# line_follower_INCOMPLETE.net
KiCad netlist of a schematic drawn in EAGLE
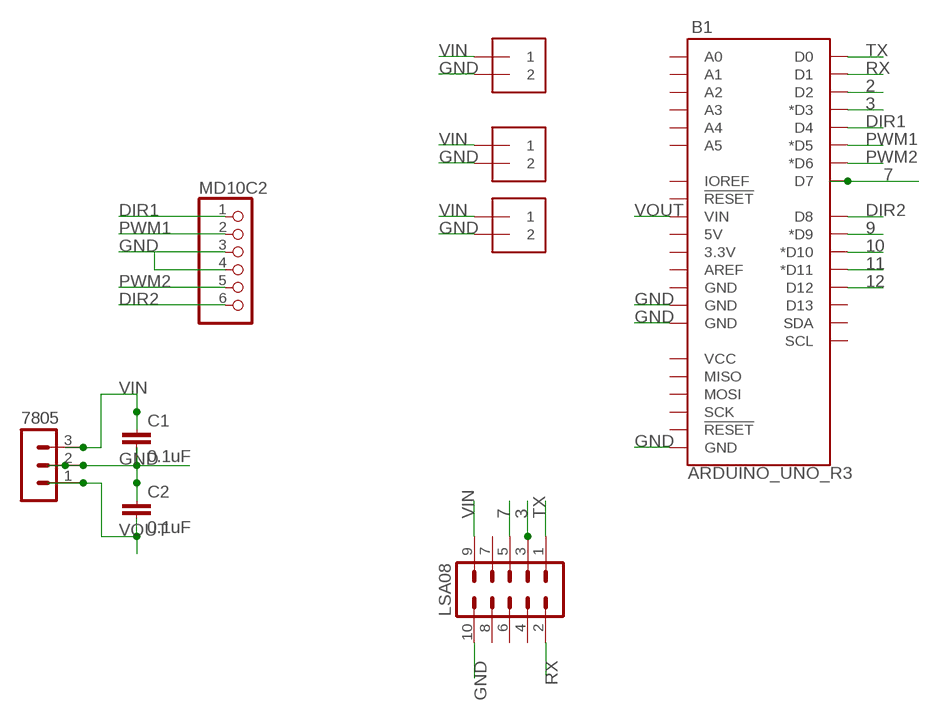
[diagram p0: schematic, sheet 1]

(export (version "E")
  (design (tool "Eeschema 10.0.6"))
  (components
    (comp (ref "7805")
      (value "MA03-1")
      (footprint "eagle-import:MA03-1")
      (libsource (lib "eagle-import") (part "MA03-1"))
    )
    (comp (ref "B1")
      (value "ARDUINO_UNO_R3")
      (footprint "eagle-import:ARDUINO_R3")
      (libsource (lib "eagle-import") (part "ARDUINO_UNO_R3"))
    )
    (comp (ref "C1")
      (value "0.1uF")
      (footprint "eagle-import:CAP-PTH-SMALL-KIT")
      (libsource (lib "eagle-import") (part "0.1UF-KIT-EZ-50V-20%"))
    )
    (comp (ref "C2")
      (value "0.1uF")
      (footprint "eagle-import:CAP-PTH-SMALL-KIT")
      (libsource (lib "eagle-import") (part "0.1UF-KIT-EZ-50V-20%"))
    )
    (comp (ref "LSA08")
      (value "MA05-2")
      (footprint "eagle-import:MA05-2")
      (libsource (lib "eagle-import") (part "MA05-2"))
    )
    (comp (ref "MD1POWER")
      (value "1X2-3.5MM")
      (footprint "eagle-import:1X2-3.5MM")
      (libsource (lib "eagle-import") (part "1X2-3.5MM"))
    )
    (comp (ref "MD2POWER")
      (value "1X2-3.5MM")
      (footprint "eagle-import:1X2-3.5MM")
      (libsource (lib "eagle-import") (part "1X2-3.5MM"))
    )
    (comp (ref "MD10C2")
      (value "PINHD-1X6")
      (footprint "eagle-import:1X06")
      (libsource (lib "eagle-import") (part "PINHD-1X6"))
    )
    (comp (ref "POWERARDUINO")
      (value "1X2-3.5MM")
      (footprint "eagle-import:1X2-3.5MM")
      (libsource (lib "eagle-import") (part "1X2-3.5MM"))
    )
  )
  (nets
    (net (code "1") (name "/2") (class "Default")
      (node (ref "B1") (pin "D2") (pinfunction "D2_D2") (pintype "bidirectional"))
    )
    (net (code "2") (name "/3") (class "Default")
      (node (ref "B1") (pin "D3") (pinfunction "*D3_D3") (pintype "bidirectional"))
      (node (ref "LSA08") (pin "3") (pinfunction "3_3") (pintype "passive"))
    )
    (net (code "3") (name "/7") (class "Default")
      (node (ref "B1") (pin "D7") (pinfunction "D7_D7") (pintype "bidirectional"))
      (node (ref "LSA08") (pin "5") (pinfunction "5_5") (pintype "passive"))
    )
    (net (code "4") (name "/9") (class "Default")
      (node (ref "B1") (pin "D9") (pinfunction "*D9_D9") (pintype "bidirectional"))
    )
    (net (code "5") (name "/10") (class "Default")
      (node (ref "B1") (pin "D10") (pinfunction "*D10_D10") (pintype "bidirectional"))
    )
    (net (code "6") (name "/11") (class "Default")
      (node (ref "B1") (pin "D11") (pinfunction "*D11_D11") (pintype "bidirectional"))
    )
    (net (code "7") (name "/12") (class "Default")
      (node (ref "B1") (pin "D12") (pinfunction "D12_D12") (pintype "bidirectional"))
    )
    (net (code "8") (name "/DIR1") (class "Default")
      (node (ref "B1") (pin "D4") (pinfunction "D4_D4") (pintype "bidirectional"))
      (node (ref "MD10C2") (pin "1") (pinfunction "1_1") (pintype "passive"))
    )
    (net (code "9") (name "/DIR2") (class "Default")
      (node (ref "B1") (pin "D8") (pinfunction "D8_D8") (pintype "bidirectional"))
      (node (ref "MD10C2") (pin "6") (pinfunction "6_6") (pintype "passive"))
    )
    (net (code "10") (name "/GND") (class "Default")
      (node (ref "7805") (pin "2") (pinfunction "2_2") (pintype "passive"))
      (node (ref "B1") (pin "GND@1") (pinfunction "GND_GND@1") (pintype "bidirectional"))
      (node (ref "B1") (pin "GND@2") (pinfunction "GND_GND@2") (pintype "bidirectional"))
      (node (ref "B1") (pin "GND@3") (pinfunction "GND_GND@3") (pintype "bidirectional"))
      (node (ref "C1") (pin "2") (pinfunction "2_2") (pintype "passive"))
      (node (ref "C2") (pin "1") (pinfunction "1_1") (pintype "passive"))
      (node (ref "LSA08") (pin "10") (pinfunction "10_10") (pintype "passive"))
      (node (ref "MD10C2") (pin "3") (pinfunction "3_3") (pintype "passive"))
      (node (ref "MD10C2") (pin "4") (pinfunction "4_4") (pintype "passive"))
      (node (ref "MD1POWER") (pin "2") (pinfunction "2_2") (pintype "passive"))
      (node (ref "MD2POWER") (pin "2") (pinfunction "2_2") (pintype "passive"))
      (node (ref "POWERARDUINO") (pin "2") (pinfunction "2_2") (pintype "passive"))
    )
    (net (code "11") (name "/PWM1") (class "Default")
      (node (ref "B1") (pin "D5") (pinfunction "*D5_D5") (pintype "bidirectional"))
      (node (ref "MD10C2") (pin "2") (pinfunction "2_2") (pintype "passive"))
    )
    (net (code "12") (name "/PWM2") (class "Default")
      (node (ref "B1") (pin "D6") (pinfunction "*D6_D6") (pintype "bidirectional"))
      (node (ref "MD10C2") (pin "5") (pinfunction "5_5") (pintype "passive"))
    )
    (net (code "13") (name "/RX") (class "Default")
      (node (ref "B1") (pin "D1") (pinfunction "D1_D1") (pintype "bidirectional"))
      (node (ref "LSA08") (pin "2") (pinfunction "2_2") (pintype "passive"))
    )
    (net (code "14") (name "/TX") (class "Default")
      (node (ref "B1") (pin "D0") (pinfunction "D0_D0") (pintype "bidirectional"))
      (node (ref "LSA08") (pin "1") (pinfunction "1_1") (pintype "passive"))
    )
    (net (code "15") (name "/VIN") (class "Default")
      (node (ref "7805") (pin "3") (pinfunction "3_3") (pintype "passive"))
      (node (ref "C1") (pin "1") (pinfunction "1_1") (pintype "passive"))
      (node (ref "LSA08") (pin "9") (pinfunction "9_9") (pintype "passive"))
      (node (ref "MD1POWER") (pin "1") (pinfunction "1_1") (pintype "passive"))
      (node (ref "MD2POWER") (pin "1") (pinfunction "1_1") (pintype "passive"))
      (node (ref "POWERARDUINO") (pin "1") (pinfunction "1_1") (pintype "passive"))
    )
    (net (code "16") (name "/VOUT") (class "Default")
      (node (ref "7805") (pin "1") (pinfunction "1_1") (pintype "passive"))
      (node (ref "B1") (pin "VIN") (pinfunction "VIN_VIN") (pintype "bidirectional"))
      (node (ref "C2") (pin "2") (pinfunction "2_2") (pintype "passive"))
    )
    (net (code "17") (name "unconnected-(B1-GND-PadGND@4)") (class "Default")
      (node (ref "B1") (pin "GND@4") (pinfunction "GND_GND@4") (pintype "bidirectional"))
    )
    (net (code "18") (name "unconnected-(B1-Pad3.3V)") (class "Default")
      (node (ref "B1") (pin "3.3V") (pinfunction "3.3V_3.3V") (pintype "bidirectional"))
    )
    (net (code "19") (name "unconnected-(B1-Pad5V)") (class "Default")
      (node (ref "B1") (pin "5V") (pinfunction "5V_5V") (pintype "bidirectional"))
    )
    (net (code "20") (name "unconnected-(B1-PadA0)") (class "Default")
      (node (ref "B1") (pin "A0") (pinfunction "A0_A0") (pintype "bidirectional"))
    )
    (net (code "21") (name "unconnected-(B1-PadA1)") (class "Default")
      (node (ref "B1") (pin "A1") (pinfunction "A1_A1") (pintype "bidirectional"))
    )
    (net (code "22") (name "unconnected-(B1-PadA2)") (class "Default")
      (node (ref "B1") (pin "A2") (pinfunction "A2_A2") (pintype "bidirectional"))
    )
    (net (code "23") (name "unconnected-(B1-PadA3)") (class "Default")
      (node (ref "B1") (pin "A3") (pinfunction "A3_A3") (pintype "bidirectional"))
    )
    (net (code "24") (name "unconnected-(B1-PadA4)") (class "Default")
      (node (ref "B1") (pin "A4") (pinfunction "A4_A4") (pintype "bidirectional"))
    )
    (net (code "25") (name "unconnected-(B1-PadA5)") (class "Default")
      (node (ref "B1") (pin "A5") (pinfunction "A5_A5") (pintype "bidirectional"))
    )
    (net (code "26") (name "unconnected-(B1-PadAREF)") (class "Default")
      (node (ref "B1") (pin "AREF") (pinfunction "AREF_AREF") (pintype "bidirectional"))
    )
    (net (code "27") (name "unconnected-(B1-PadD13)") (class "Default")
      (node (ref "B1") (pin "D13") (pinfunction "D13_D13") (pintype "bidirectional"))
    )
    (net (code "28") (name "unconnected-(B1-PadIOREF)") (class "Default")
      (node (ref "B1") (pin "IOREF") (pinfunction "IOREF_IOREF") (pintype "bidirectional"))
    )
    (net (code "29") (name "unconnected-(B1-PadMISO)") (class "Default")
      (node (ref "B1") (pin "MISO") (pinfunction "MISO_MISO") (pintype "bidirectional"))
    )
    (net (code "30") (name "unconnected-(B1-PadMOSI)") (class "Default")
      (node (ref "B1") (pin "MOSI") (pinfunction "MOSI_MOSI") (pintype "bidirectional"))
    )
    (net (code "31") (name "unconnected-(B1-PadSCK)") (class "Default")
      (node (ref "B1") (pin "SCK") (pinfunction "SCK_SCK") (pintype "bidirectional"))
    )
    (net (code "32") (name "unconnected-(B1-PadSCL)") (class "Default")
      (node (ref "B1") (pin "SCL") (pinfunction "SCL_SCL") (pintype "bidirectional"))
    )
    (net (code "33") (name "unconnected-(B1-PadSDA)") (class "Default")
      (node (ref "B1") (pin "SDA") (pinfunction "SDA_SDA") (pintype "bidirectional"))
    )
    (net (code "34") (name "unconnected-(B1-PadVCC)") (class "Default")
      (node (ref "B1") (pin "VCC") (pinfunction "VCC_VCC") (pintype "bidirectional"))
    )
    (net (code "35") (name "unconnected-(B1-~{RESET}-PadRESET@1)") (class "Default")
      (node (ref "B1") (pin "RESET@1") (pinfunction "~{RESET}_RESET@1") (pintype "bidirectional"))
    )
    (net (code "36") (name "unconnected-(B1-~{RESET}-PadRESET@2)") (class "Default")
      (node (ref "B1") (pin "RESET@2") (pinfunction "~{RESET}_RESET@2") (pintype "bidirectional"))
    )
    (net (code "37") (name "unconnected-(LSA08-Pad4)") (class "Default")
      (node (ref "LSA08") (pin "4") (pinfunction "4_4") (pintype "passive"))
    )
    (net (code "38") (name "unconnected-(LSA08-Pad6)") (class "Default")
      (node (ref "LSA08") (pin "6") (pinfunction "6_6") (pintype "passive"))
    )
    (net (code "39") (name "unconnected-(LSA08-Pad7)") (class "Default")
      (node (ref "LSA08") (pin "7") (pinfunction "7_7") (pintype "passive"))
    )
    (net (code "40") (name "unconnected-(LSA08-Pad8)") (class "Default")
      (node (ref "LSA08") (pin "8") (pinfunction "8_8") (pintype "passive"))
    )
  )
)
